# Sheet1.net
KiCad netlist of a schematic drawn in Altium Designer
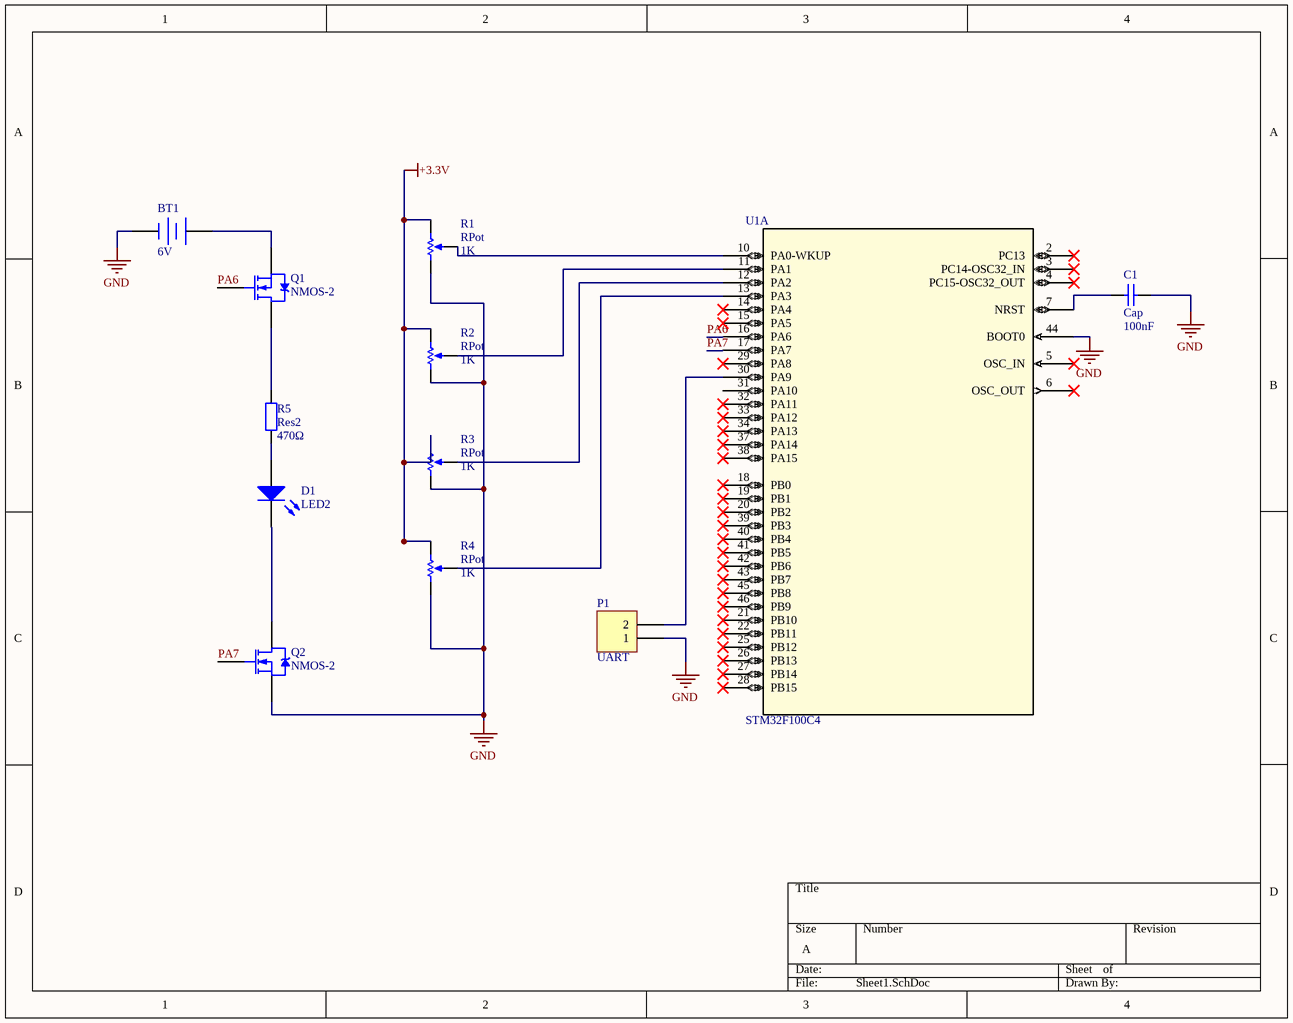
[diagram p0: Sheet1.SchDoc]

(export (version "E")
  (design (tool "Eeschema 10.0.6"))
  (components
    (comp (ref "BT1")
      (value "6V")
      (footprint "BAT-2")
      (description "Multicell Battery")
      (fields (field (name "PUBLISHER") "Altium Limited"))
      (libsource (lib "Miscellaneous Devices") (part "Battery"))
    )
    (comp (ref "C1")
      (value "Cap")
      (footprint "RAD-0.3")
      (description "Capacitor")
      (fields (field (name "ALTIUM_VALUE") "100nF") (field (name "PUBLISHER") "Altium Limited"))
      (libsource (lib "Miscellaneous Devices") (part "Cap"))
    )
    (comp (ref "D1")
      (value "LED2")
      (footprint "3.2X1.6X1.1")
      (description "Typical RED, GREEN, YELLOW, AMBER GaAs LED")
      (fields (field (name "PUBLISHER") "Altium Limited"))
      (libsource (lib "Miscellaneous Devices") (part "LED2"))
    )
    (comp (ref "P1")
      (value "UART")
      (footprint "HDR1X2")
      (description "Header, 2-Pin")
      (fields (field (name "PUBLISHER") "Altium Limited"))
      (libsource (lib "Miscellaneous Connectors") (part "Header 2"))
    )
    (comp (ref "Q1")
      (value "NMOS-2")
      (footprint "TO-220AB")
      (description "N-Channel Power MOSFET")
      (fields (field (name "PUBLISHER") "Altium Limited"))
      (libsource (lib "Miscellaneous Devices") (part "NMOS-2"))
    )
    (comp (ref "Q2")
      (value "NMOS-2")
      (footprint "TO-220AB")
      (description "N-Channel Power MOSFET")
      (fields (field (name "PUBLISHER") "Altium Limited"))
      (libsource (lib "Miscellaneous Devices") (part "NMOS-2"))
    )
    (comp (ref "R1")
      (value "RPot")
      (footprint "VR5")
      (description "Potentiometer")
      (fields (field (name "ALTIUM_VALUE") "1K") (field (name "PUBLISHER") "Altium Limited"))
      (libsource (lib "Miscellaneous Devices") (part "RPot"))
    )
    (comp (ref "R2")
      (value "RPot")
      (footprint "VR5")
      (description "Potentiometer")
      (fields (field (name "ALTIUM_VALUE") "1K") (field (name "PUBLISHER") "Altium Limited"))
      (libsource (lib "Miscellaneous Devices") (part "RPot"))
    )
    (comp (ref "R3")
      (value "RPot")
      (footprint "VR5")
      (description "Potentiometer")
      (fields (field (name "ALTIUM_VALUE") "1K") (field (name "PUBLISHER") "Altium Limited"))
      (libsource (lib "Miscellaneous Devices") (part "RPot"))
    )
    (comp (ref "R4")
      (value "RPot")
      (footprint "VR5")
      (description "Potentiometer")
      (fields (field (name "ALTIUM_VALUE") "1K") (field (name "PUBLISHER") "Altium Limited"))
      (libsource (lib "Miscellaneous Devices") (part "RPot"))
    )
    (comp (ref "R5")
      (value "Res2")
      (footprint "AXIAL-0.4")
      (description "Resistor")
      (fields (field (name "ALTIUM_VALUE") "470Ω") (field (name "PUBLISHER") "Altium Limited"))
      (libsource (lib "Miscellaneous Devices") (part "Res2"))
    )
    (comp (ref "U1")
      (value "STM32F100C4")
      (footprint "LQFP48-7x7mm")
      (fields
        (field (name "MANUFACTURER_PART_NUMBER") "STM32F100C4T6B")
        (field (name "COPYRIGHT") "Copyright (C) 2025 Ultra Librarian. All rights reserved.")
      )
      (libsource (lib "STM32F100C4T6B") (part "STM32F100C4T6B"))
    )
  )
  (nets
    (net (code "1") (name "+3.3V") (class "Default")
      (node (ref "R1") (pin "2") (pinfunction "BOT_2") (pintype "passive"))
      (node (ref "R2") (pin "2") (pinfunction "BOT_2") (pintype "passive"))
      (node (ref "R3") (pin "2") (pinfunction "BOT_2") (pintype "passive"))
      (node (ref "R4") (pin "2") (pinfunction "BOT_2") (pintype "passive"))
    )
    (net (code "2") (name "/PA6") (class "Default")
      (node (ref "Q1") (pin "1") (pinfunction "G_1") (pintype "passive"))
      (node (ref "U1") (pin "16") (pinfunction "PA6_16") (pintype "bidirectional"))
    )
    (net (code "3") (name "/PA7") (class "Default")
      (node (ref "Q2") (pin "1") (pinfunction "G_1") (pintype "passive"))
      (node (ref "U1") (pin "17") (pinfunction "PA7_17") (pintype "bidirectional"))
    )
    (net (code "4") (name "GND") (class "Default")
      (node (ref "BT1") (pin "2") (pinfunction "-_2") (pintype "passive"))
      (node (ref "C1") (pin "2") (pinfunction "2_2") (pintype "passive"))
      (node (ref "P1") (pin "1") (pinfunction "1_1") (pintype "passive"))
      (node (ref "Q2") (pin "3") (pinfunction "S_3") (pintype "passive"))
      (node (ref "R1") (pin "1") (pinfunction "TOP_1") (pintype "passive"))
      (node (ref "R2") (pin "1") (pinfunction "TOP_1") (pintype "passive"))
      (node (ref "R3") (pin "1") (pinfunction "TOP_1") (pintype "passive"))
      (node (ref "R4") (pin "1") (pinfunction "TOP_1") (pintype "passive"))
      (node (ref "U1") (pin "44") (pinfunction "BOOT0_44") (pintype "input"))
    )
    (net (code "5") (name "Net-(BT1-+)") (class "Default")
      (node (ref "BT1") (pin "1") (pinfunction "+_1") (pintype "passive"))
      (node (ref "Q1") (pin "3") (pinfunction "S_3") (pintype "passive"))
    )
    (net (code "6") (name "Net-(D1-A)") (class "Default")
      (node (ref "D1") (pin "1") (pinfunction "A_1") (pintype "passive"))
      (node (ref "R5") (pin "1") (pinfunction "1_1") (pintype "passive"))
    )
    (net (code "7") (name "Net-(D1-K)") (class "Default")
      (node (ref "D1") (pin "2") (pinfunction "K_2") (pintype "passive"))
      (node (ref "Q2") (pin "2") (pinfunction "D_2") (pintype "passive"))
    )
    (net (code "8") (name "Net-(Q1-D)") (class "Default")
      (node (ref "Q1") (pin "2") (pinfunction "D_2") (pintype "passive"))
      (node (ref "R5") (pin "2") (pinfunction "2_2") (pintype "passive"))
    )
    (net (code "9") (name "Net-(R1-TAP)") (class "Default")
      (node (ref "R1") (pin "3") (pinfunction "TAP_3") (pintype "passive"))
      (node (ref "U1") (pin "10") (pinfunction "PA0-WKUP_10") (pintype "bidirectional"))
    )
    (net (code "10") (name "Net-(R2-TAP)") (class "Default")
      (node (ref "R2") (pin "3") (pinfunction "TAP_3") (pintype "passive"))
      (node (ref "U1") (pin "11") (pinfunction "PA1_11") (pintype "bidirectional"))
    )
    (net (code "11") (name "Net-(R3-TAP)") (class "Default")
      (node (ref "R3") (pin "3") (pinfunction "TAP_3") (pintype "passive"))
      (node (ref "U1") (pin "12") (pinfunction "PA2_12") (pintype "bidirectional"))
    )
    (net (code "12") (name "Net-(R4-TAP)") (class "Default")
      (node (ref "R4") (pin "3") (pinfunction "TAP_3") (pintype "passive"))
      (node (ref "U1") (pin "13") (pinfunction "PA3_13") (pintype "bidirectional"))
    )
    (net (code "13") (name "Net-(U1A-NRST)") (class "Default")
      (node (ref "C1") (pin "1") (pinfunction "1_1") (pintype "passive"))
      (node (ref "U1") (pin "7") (pinfunction "NRST_7") (pintype "bidirectional"))
    )
    (net (code "14") (name "Net-(U1A-PA9)") (class "Default")
      (node (ref "P1") (pin "2") (pinfunction "2_2") (pintype "passive"))
      (node (ref "U1") (pin "30") (pinfunction "PA9_30") (pintype "bidirectional"))
    )
    (net (code "15") (name "unconnected-(U1A-OSC_IN-Pad5)") (class "Default")
      (node (ref "U1") (pin "5") (pinfunction "OSC_IN_5") (pintype "input+no_connect"))
    )
    (net (code "16") (name "unconnected-(U1A-OSC_OUT-Pad6)") (class "Default")
      (node (ref "U1") (pin "6") (pinfunction "OSC_OUT_6") (pintype "output+no_connect"))
    )
    (net (code "17") (name "unconnected-(U1A-PA4-Pad14)") (class "Default")
      (node (ref "U1") (pin "14") (pinfunction "PA4_14") (pintype "bidirectional+no_connect"))
    )
    (net (code "18") (name "unconnected-(U1A-PA5-Pad15)") (class "Default")
      (node (ref "U1") (pin "15") (pinfunction "PA5_15") (pintype "bidirectional+no_connect"))
    )
    (net (code "19") (name "unconnected-(U1A-PA8-Pad29)") (class "Default")
      (node (ref "U1") (pin "29") (pinfunction "PA8_29") (pintype "bidirectional+no_connect"))
    )
    (net (code "20") (name "unconnected-(U1A-PA10-Pad31)") (class "Default")
      (node (ref "U1") (pin "31") (pinfunction "PA10_31") (pintype "bidirectional"))
    )
    (net (code "21") (name "unconnected-(U1A-PA11-Pad32)") (class "Default")
      (node (ref "U1") (pin "32") (pinfunction "PA11_32") (pintype "bidirectional+no_connect"))
    )
    (net (code "22") (name "unconnected-(U1A-PA12-Pad33)") (class "Default")
      (node (ref "U1") (pin "33") (pinfunction "PA12_33") (pintype "bidirectional+no_connect"))
    )
    (net (code "23") (name "unconnected-(U1A-PA13-Pad34)") (class "Default")
      (node (ref "U1") (pin "34") (pinfunction "PA13_34") (pintype "bidirectional+no_connect"))
    )
    (net (code "24") (name "unconnected-(U1A-PA14-Pad37)") (class "Default")
      (node (ref "U1") (pin "37") (pinfunction "PA14_37") (pintype "bidirectional+no_connect"))
    )
    (net (code "25") (name "unconnected-(U1A-PA15-Pad38)") (class "Default")
      (node (ref "U1") (pin "38") (pinfunction "PA15_38") (pintype "bidirectional+no_connect"))
    )
    (net (code "26") (name "unconnected-(U1A-PB0-Pad18)") (class "Default")
      (node (ref "U1") (pin "18") (pinfunction "PB0_18") (pintype "bidirectional+no_connect"))
    )
    (net (code "27") (name "unconnected-(U1A-PB1-Pad19)") (class "Default")
      (node (ref "U1") (pin "19") (pinfunction "PB1_19") (pintype "bidirectional+no_connect"))
    )
    (net (code "28") (name "unconnected-(U1A-PB2-Pad20)") (class "Default")
      (node (ref "U1") (pin "20") (pinfunction "PB2_20") (pintype "bidirectional+no_connect"))
    )
    (net (code "29") (name "unconnected-(U1A-PB3-Pad39)") (class "Default")
      (node (ref "U1") (pin "39") (pinfunction "PB3_39") (pintype "bidirectional+no_connect"))
    )
    (net (code "30") (name "unconnected-(U1A-PB4-Pad40)") (class "Default")
      (node (ref "U1") (pin "40") (pinfunction "PB4_40") (pintype "bidirectional+no_connect"))
    )
    (net (code "31") (name "unconnected-(U1A-PB5-Pad41)") (class "Default")
      (node (ref "U1") (pin "41") (pinfunction "PB5_41") (pintype "bidirectional+no_connect"))
    )
    (net (code "32") (name "unconnected-(U1A-PB6-Pad42)") (class "Default")
      (node (ref "U1") (pin "42") (pinfunction "PB6_42") (pintype "bidirectional+no_connect"))
    )
    (net (code "33") (name "unconnected-(U1A-PB7-Pad43)") (class "Default")
      (node (ref "U1") (pin "43") (pinfunction "PB7_43") (pintype "bidirectional+no_connect"))
    )
    (net (code "34") (name "unconnected-(U1A-PB8-Pad45)") (class "Default")
      (node (ref "U1") (pin "45") (pinfunction "PB8_45") (pintype "bidirectional+no_connect"))
    )
    (net (code "35") (name "unconnected-(U1A-PB9-Pad46)") (class "Default")
      (node (ref "U1") (pin "46") (pinfunction "PB9_46") (pintype "bidirectional+no_connect"))
    )
    (net (code "36") (name "unconnected-(U1A-PB10-Pad21)") (class "Default")
      (node (ref "U1") (pin "21") (pinfunction "PB10_21") (pintype "bidirectional+no_connect"))
    )
    (net (code "37") (name "unconnected-(U1A-PB11-Pad22)") (class "Default")
      (node (ref "U1") (pin "22") (pinfunction "PB11_22") (pintype "bidirectional+no_connect"))
    )
    (net (code "38") (name "unconnected-(U1A-PB12-Pad25)") (class "Default")
      (node (ref "U1") (pin "25") (pinfunction "PB12_25") (pintype "bidirectional+no_connect"))
    )
    (net (code "39") (name "unconnected-(U1A-PB13-Pad26)") (class "Default")
      (node (ref "U1") (pin "26") (pinfunction "PB13_26") (pintype "bidirectional+no_connect"))
    )
    (net (code "40") (name "unconnected-(U1A-PB14-Pad27)") (class "Default")
      (node (ref "U1") (pin "27") (pinfunction "PB14_27") (pintype "bidirectional+no_connect"))
    )
    (net (code "41") (name "unconnected-(U1A-PB15-Pad28)") (class "Default")
      (node (ref "U1") (pin "28") (pinfunction "PB15_28") (pintype "bidirectional+no_connect"))
    )
    (net (code "42") (name "unconnected-(U1A-PC13-Pad2)") (class "Default")
      (node (ref "U1") (pin "2") (pinfunction "PC13_2") (pintype "bidirectional+no_connect"))
    )
    (net (code "43") (name "unconnected-(U1A-PC14-OSC32_IN-Pad3)") (class "Default")
      (node (ref "U1") (pin "3") (pinfunction "PC14-OSC32_IN_3") (pintype "bidirectional+no_connect"))
    )
    (net (code "44") (name "unconnected-(U1A-PC15-OSC32_OUT-Pad4)") (class "Default")
      (node (ref "U1") (pin "4") (pinfunction "PC15-OSC32_OUT_4") (pintype "bidirectional+no_connect"))
    )
  )
)
